# Controlador_Aforo.net
KiCad netlist of a schematic drawn in EasyEDA
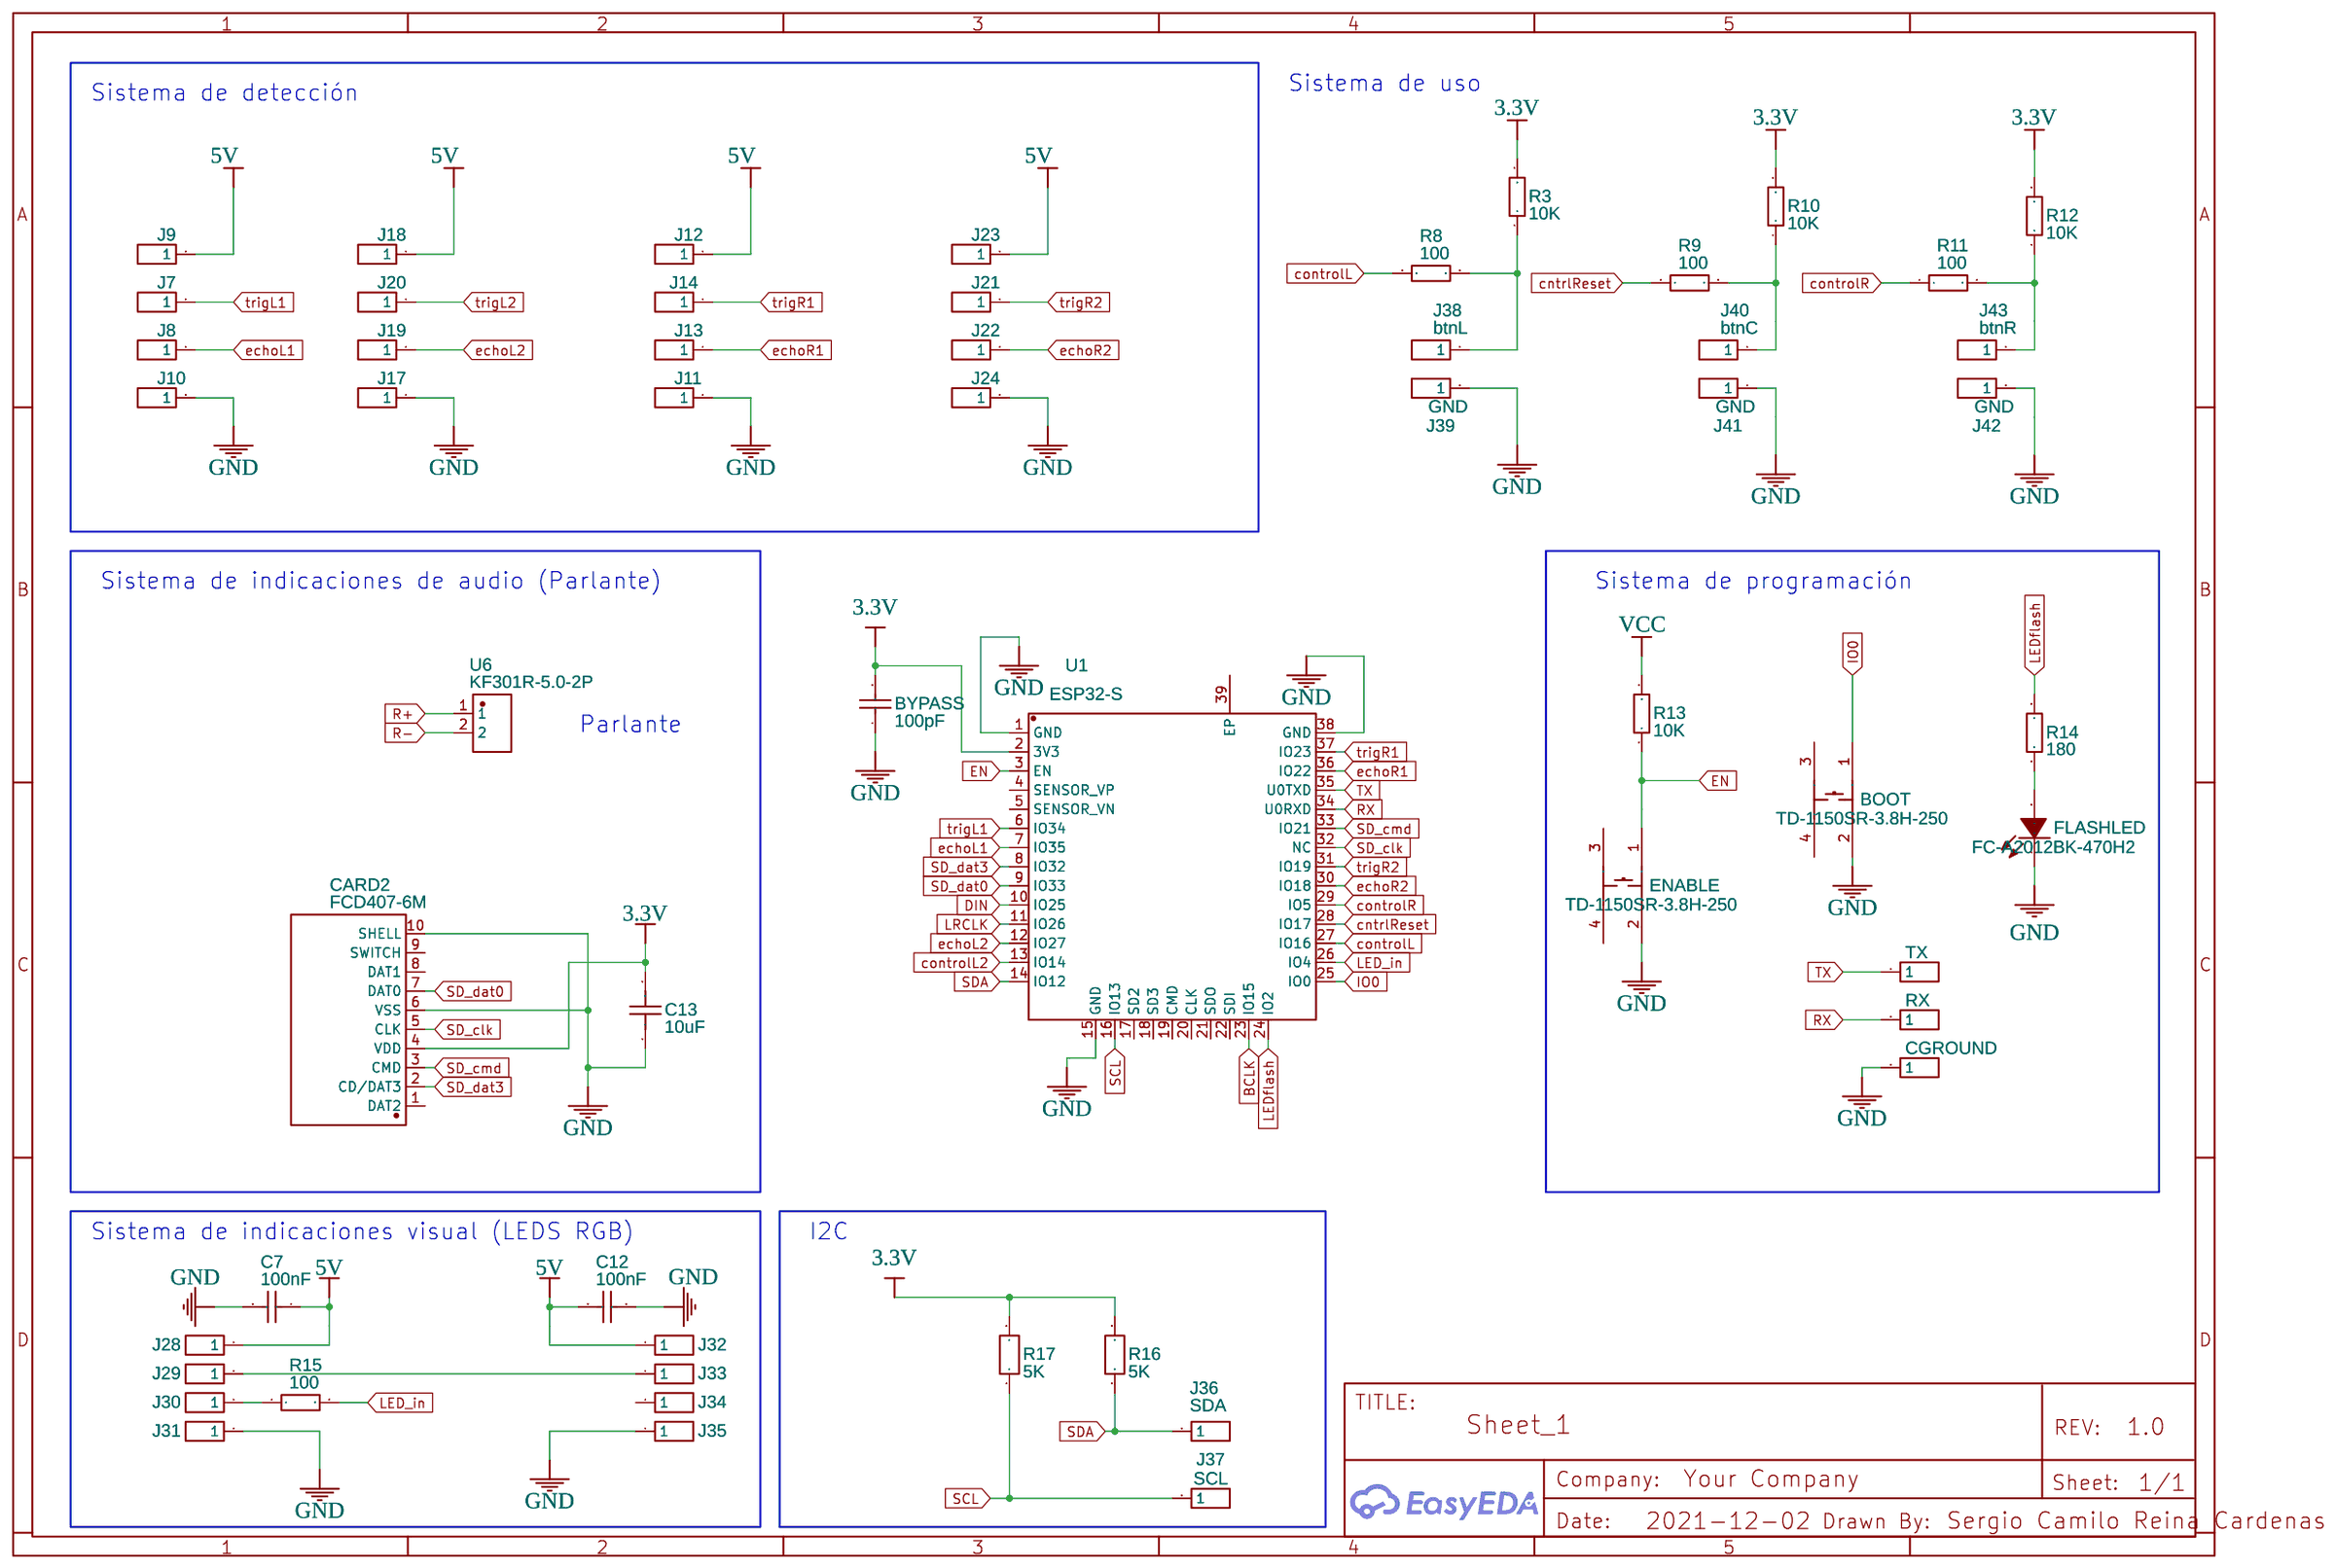
[diagram p0: Controlador_aforo]
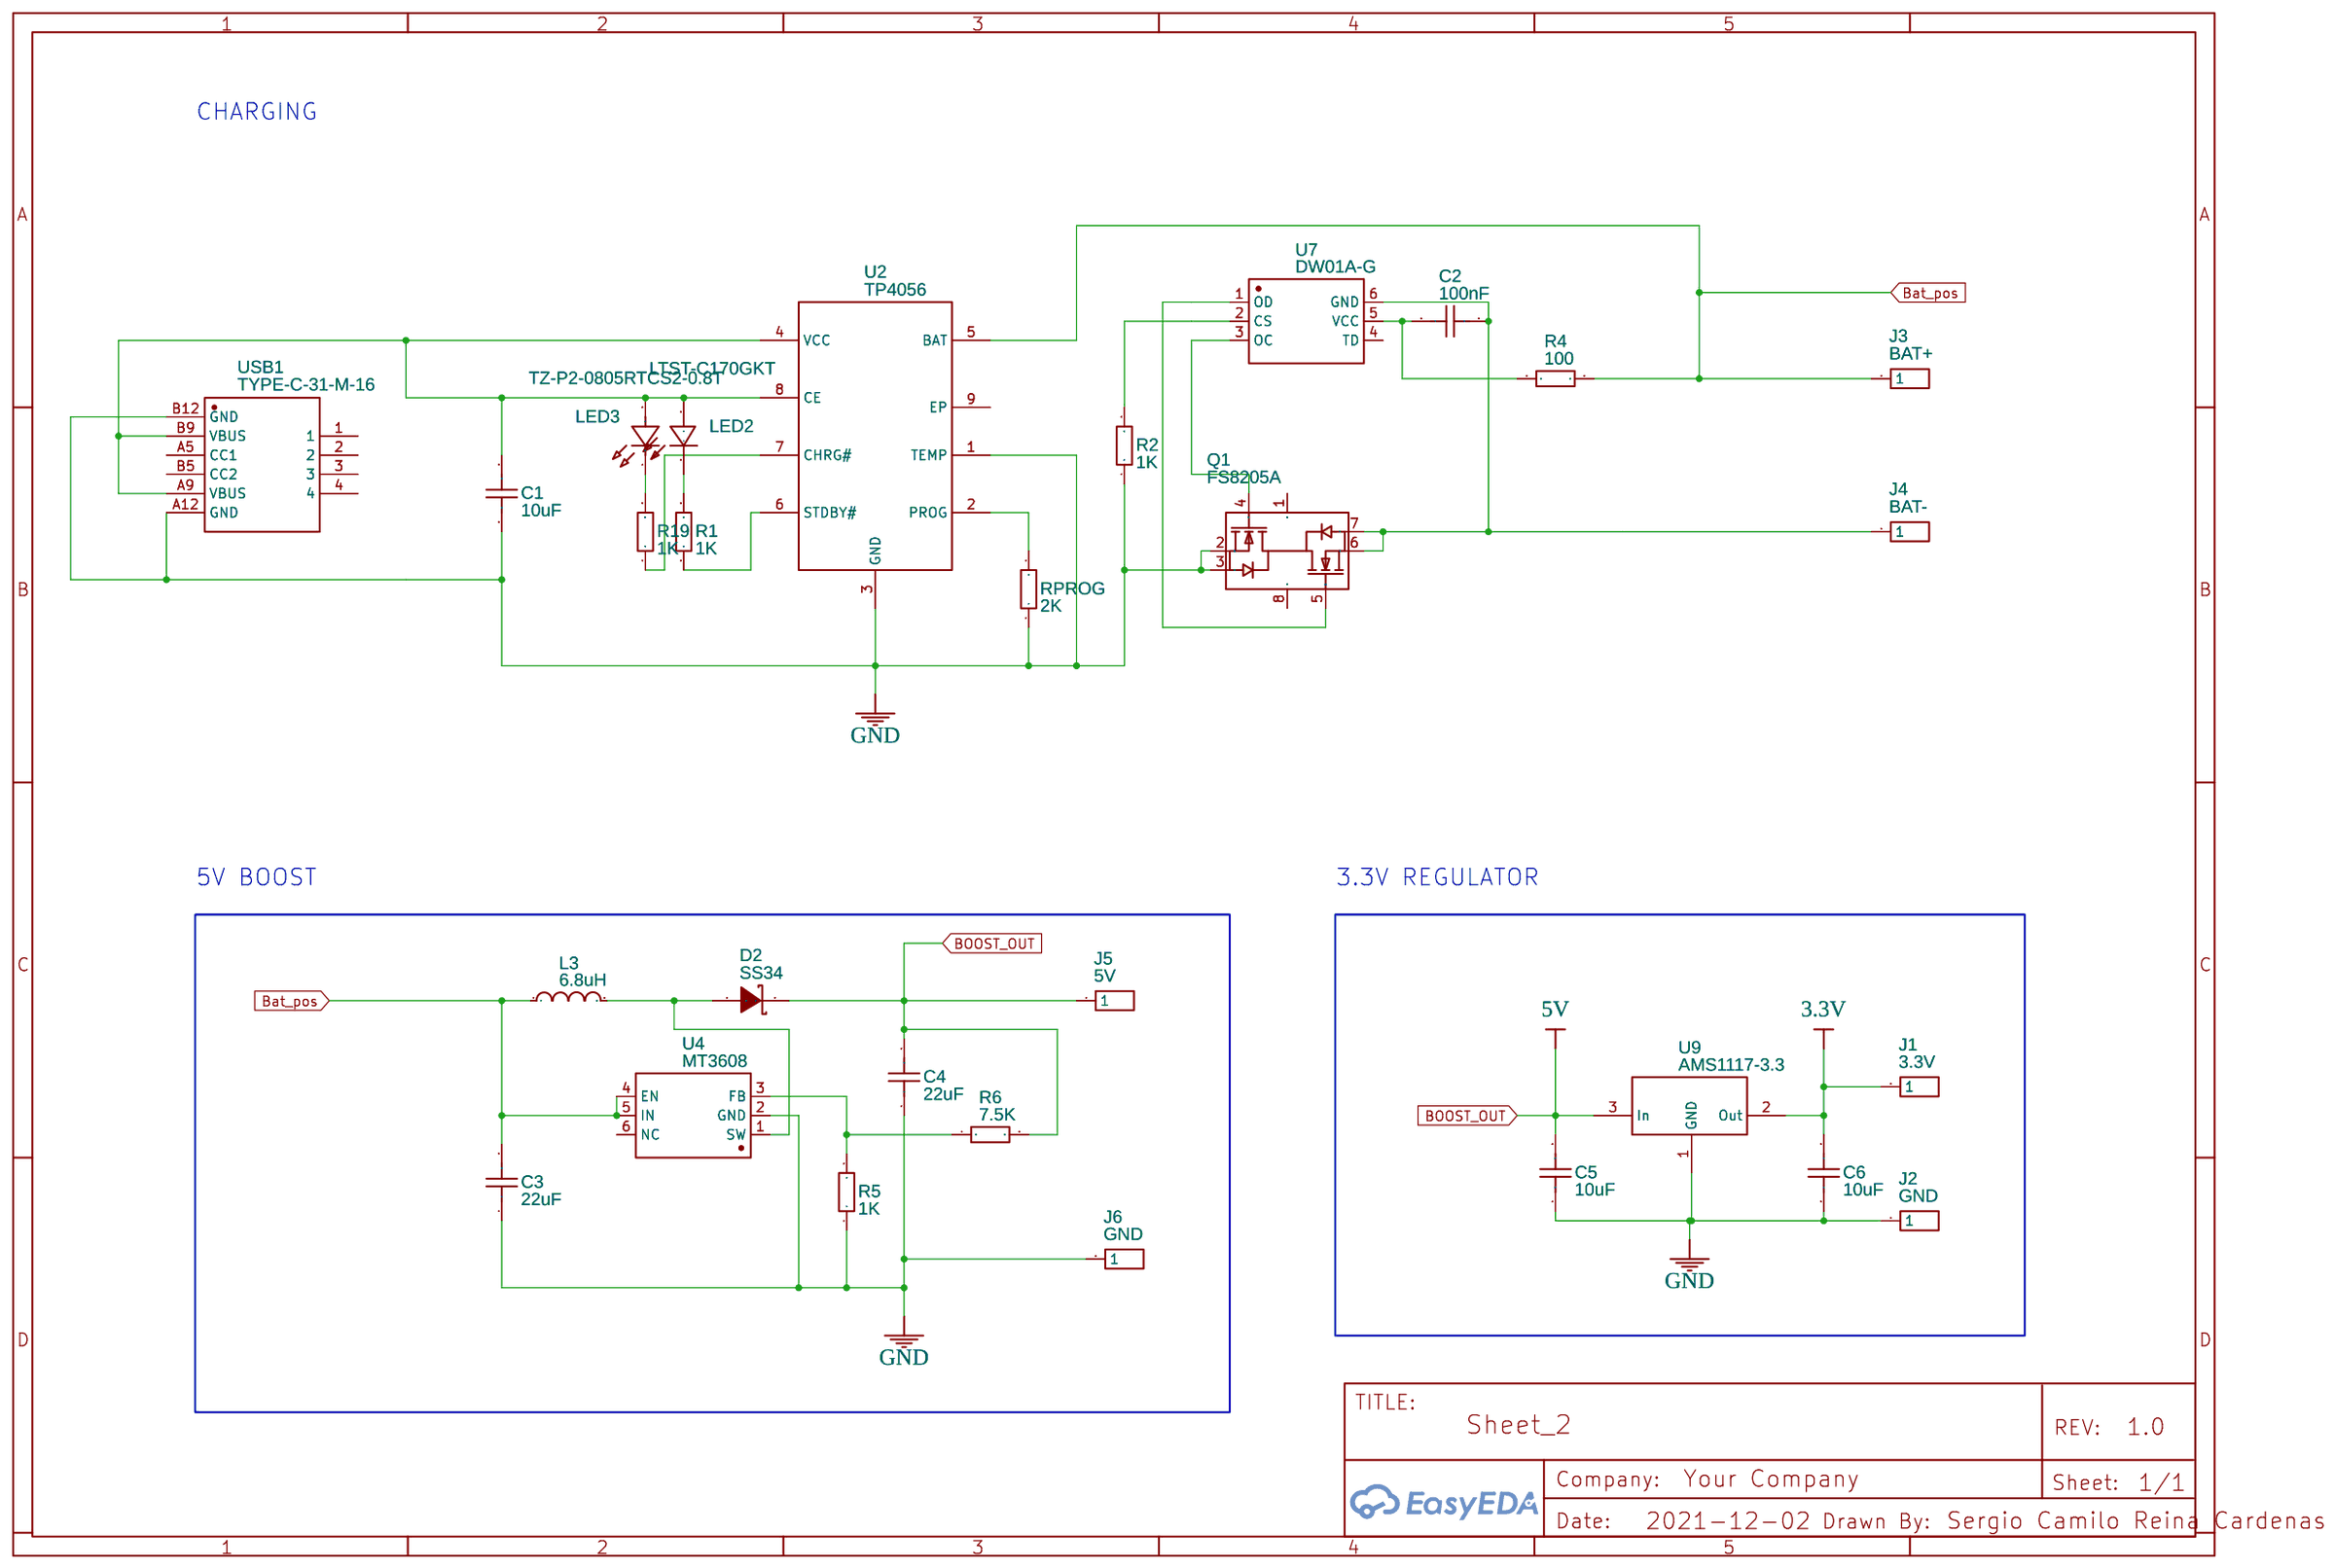
[diagram p1: Power]
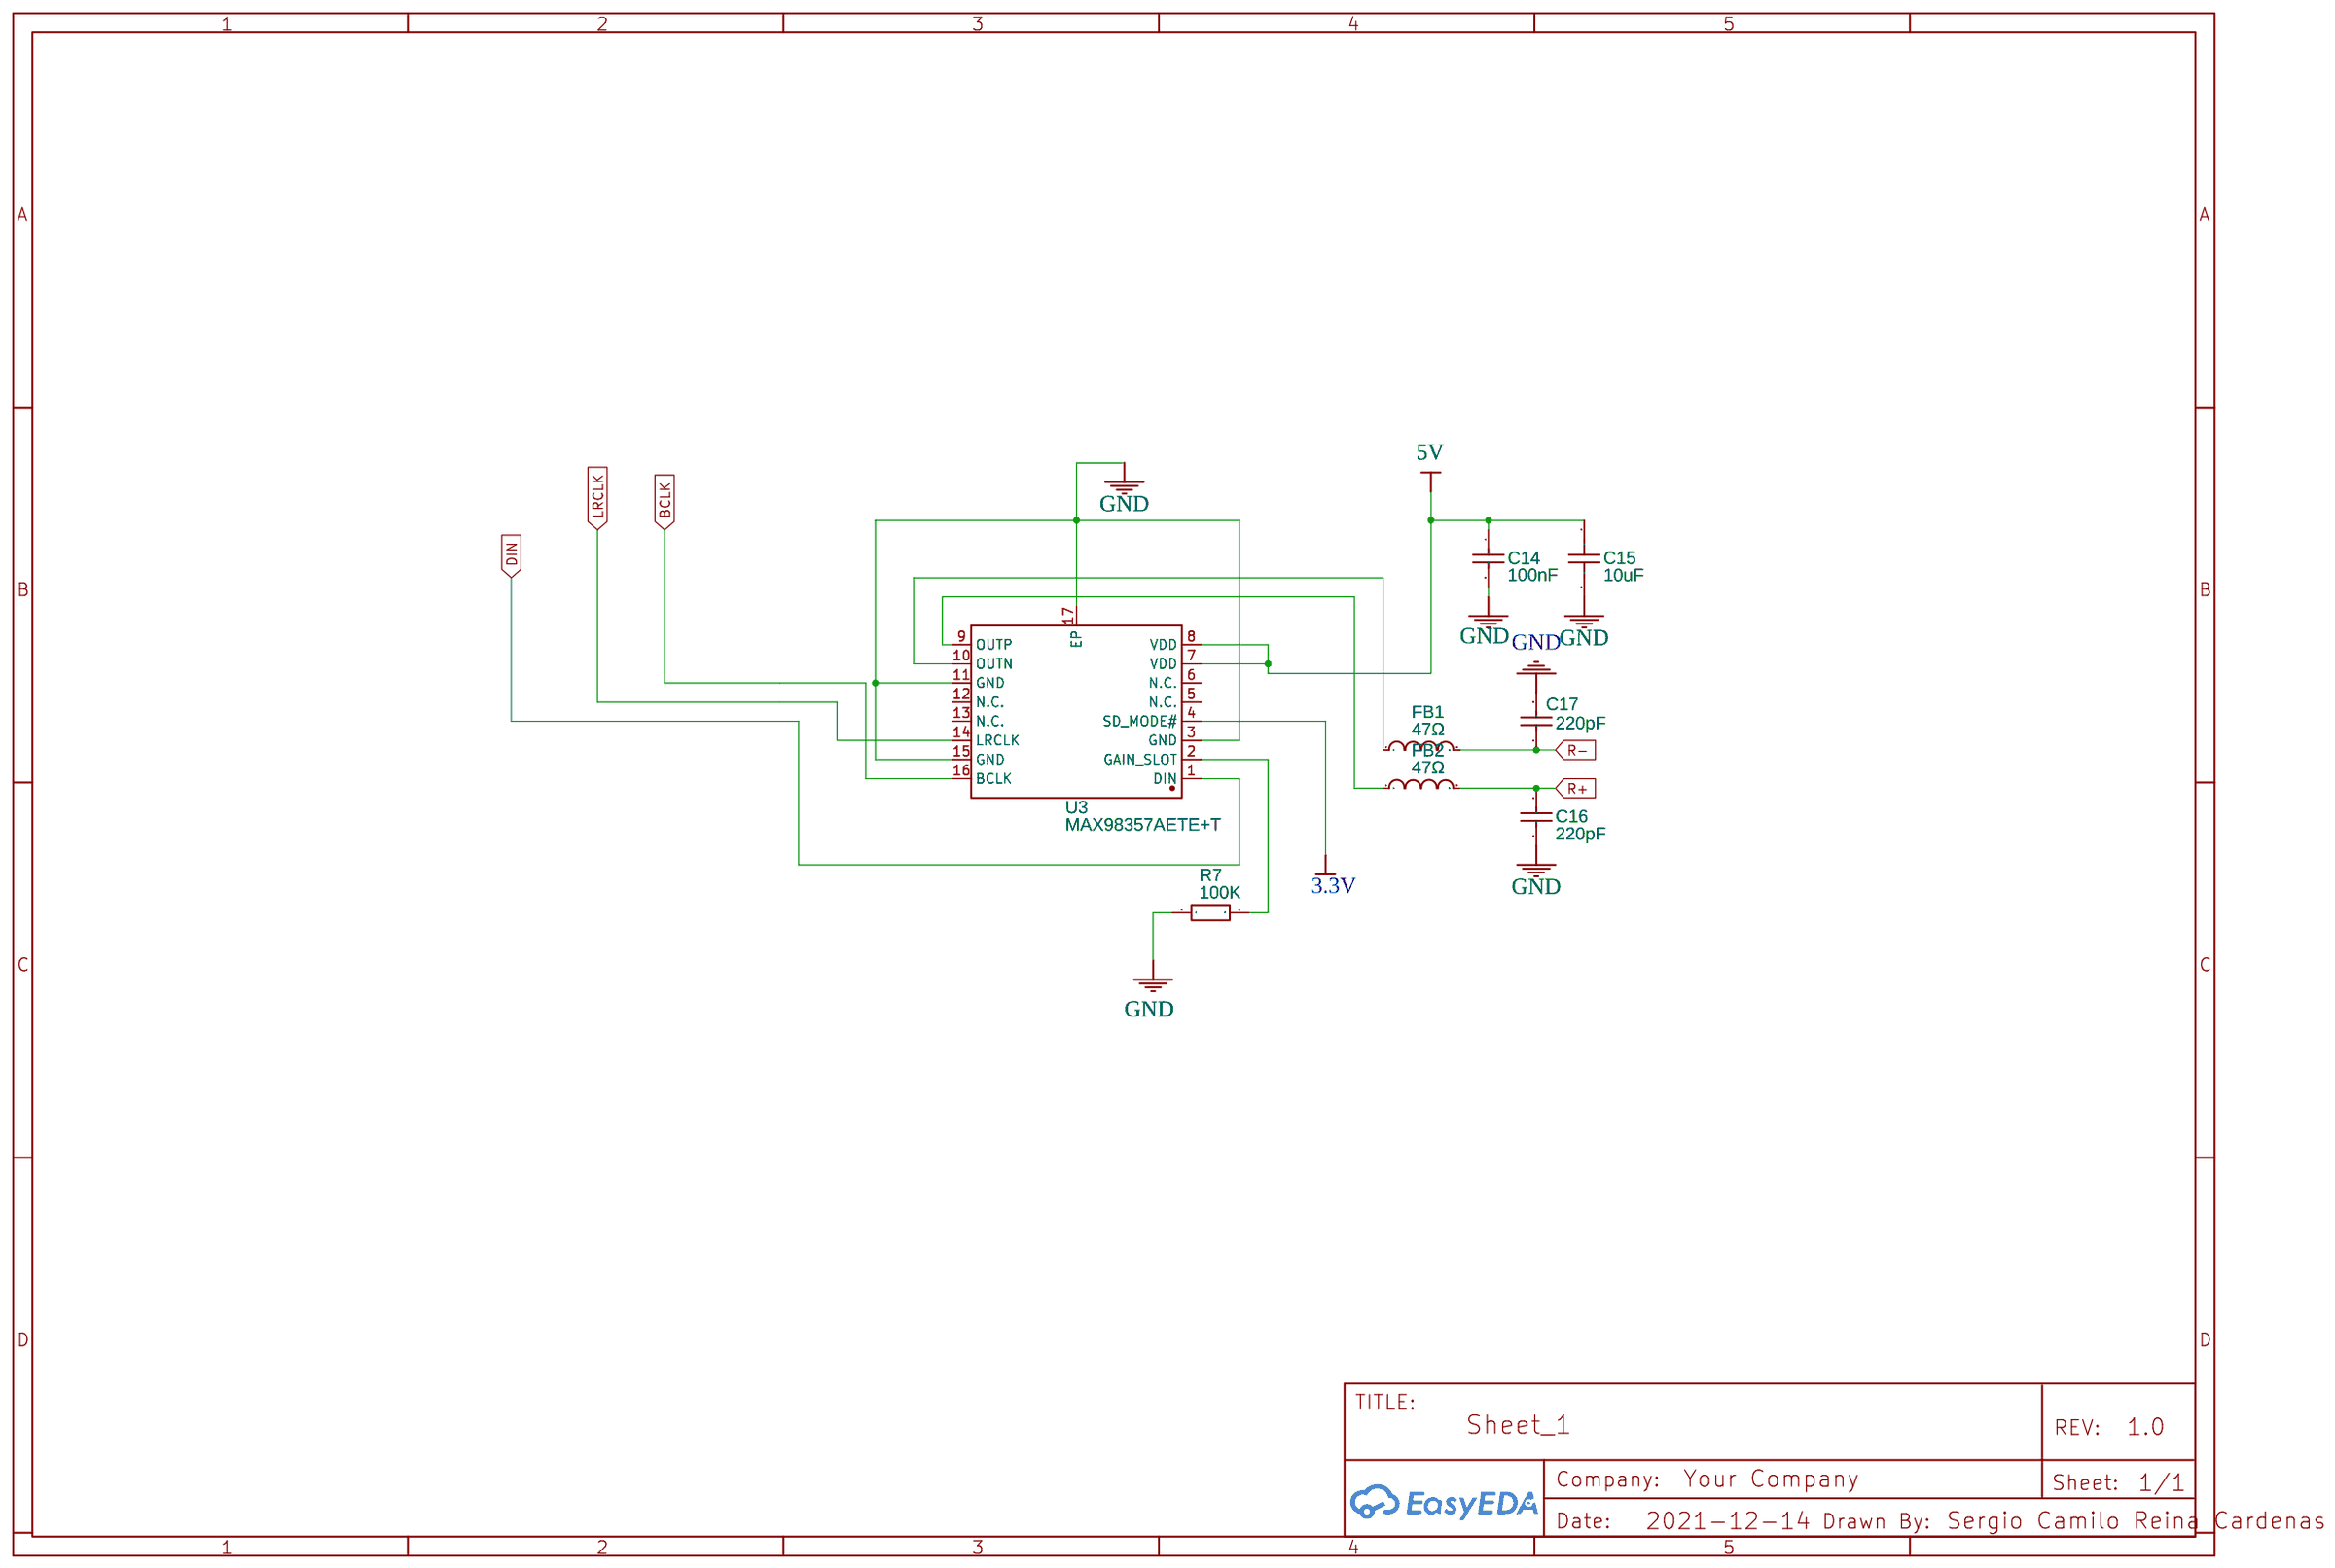
[diagram p2: Audio_amplifier]

(export (version "E")
  (design (tool "Eeschema 10.0.6"))
  (components
    (comp (ref "BOOT")
      (value "TD-1150SR-3.8H-250")
      (fields (field (name "BOM_Supplier Part") "C2905105"))
      (libsource (lib "") (part "TD-1150SR-3.8H-250_1"))
    )
    (comp (ref "BYPASS")
      (value "100pF")
      (fields
        (field (name "BOM_Manufacturer Part") "C1210N101J202T")
        (field (name "BOM_Supplier Part") "C106093")
      )
      (libsource (lib "") (part "C1210N101J202T"))
    )
    (comp (ref "C7")
      (value "100nF")
      (fields
        (field (name "BOM_Manufacturer Part") "C1210X104M501T")
        (field (name "BOM_Supplier Part") "C106106")
      )
      (libsource (lib "") (part "C1210X104M501T"))
    )
    (comp (ref "C12")
      (value "100nF")
      (fields
        (field (name "BOM_Manufacturer Part") "C1210X104M501T")
        (field (name "BOM_Supplier Part") "C106106")
      )
      (libsource (lib "") (part "C1210X104M501T"))
    )
    (comp (ref "C13")
      (value "10uF")
      (fields
        (field (name "BOM_Manufacturer Part") "0805F106M100NT")
        (field (name "BOM_Supplier Part") "C91158")
      )
      (libsource (lib "") (part "0805F106M100NT"))
    )
    (comp (ref "CARD2")
      (value "FCD407-6M")
      (fields (field (name "BOM_Supplier Part") "C456402"))
      (libsource (lib "") (part "FCD407-6M"))
    )
    (comp (ref "CGROUND")
      (value "HDR-M-2.54_1x1")
      (fields (field (name "BOM_Supplier Part") "C81276"))
      (libsource (lib "") (part "HDR-M-2.54_1x1_4"))
    )
    (comp (ref "ENABLE")
      (value "TD-1150SR-3.8H-250")
      (fields (field (name "BOM_Supplier Part") "C2905105"))
      (libsource (lib "") (part "TD-1150SR-3.8H-250"))
    )
    (comp (ref "FLASHLED")
      (value "FC-A2012BK-470H2")
      (fields (field (name "BOM_Supplier Part") "C84259"))
      (libsource (lib "") (part "FC-A2012BK-470H2"))
    )
    (comp (ref "J7")
      (value "HDR-M-2.54_1x1")
      (fields (field (name "BOM_Supplier Part") "C81276"))
      (libsource (lib "") (part "HDR-M-2.54_1x1"))
    )
    (comp (ref "J8")
      (value "HDR-M-2.54_1x1")
      (fields (field (name "BOM_Supplier Part") "C81276"))
      (libsource (lib "") (part "HDR-M-2.54_1x1"))
    )
    (comp (ref "J9")
      (value "HDR-M-2.54_1x1")
      (fields (field (name "BOM_Supplier Part") "C81276"))
      (libsource (lib "") (part "HDR-M-2.54_1x1"))
    )
    (comp (ref "J10")
      (value "HDR-M-2.54_1x1")
      (fields (field (name "BOM_Supplier Part") "C81276"))
      (libsource (lib "") (part "HDR-M-2.54_1x1"))
    )
    (comp (ref "J11")
      (value "HDR-M-2.54_1x1")
      (fields (field (name "BOM_Supplier Part") "C81276"))
      (libsource (lib "") (part "HDR-M-2.54_1x1"))
    )
    (comp (ref "J12")
      (value "HDR-M-2.54_1x1")
      (fields (field (name "BOM_Supplier Part") "C81276"))
      (libsource (lib "") (part "HDR-M-2.54_1x1"))
    )
    (comp (ref "J13")
      (value "HDR-M-2.54_1x1")
      (fields (field (name "BOM_Supplier Part") "C81276"))
      (libsource (lib "") (part "HDR-M-2.54_1x1"))
    )
    (comp (ref "J14")
      (value "HDR-M-2.54_1x1")
      (fields (field (name "BOM_Supplier Part") "C81276"))
      (libsource (lib "") (part "HDR-M-2.54_1x1"))
    )
    (comp (ref "J17")
      (value "HDR-M-2.54_1x1")
      (fields (field (name "BOM_Supplier Part") "C81276"))
      (libsource (lib "") (part "HDR-M-2.54_1x1"))
    )
    (comp (ref "J18")
      (value "HDR-M-2.54_1x1")
      (fields (field (name "BOM_Supplier Part") "C81276"))
      (libsource (lib "") (part "HDR-M-2.54_1x1"))
    )
    (comp (ref "J19")
      (value "HDR-M-2.54_1x1")
      (fields (field (name "BOM_Supplier Part") "C81276"))
      (libsource (lib "") (part "HDR-M-2.54_1x1"))
    )
    (comp (ref "J20")
      (value "HDR-M-2.54_1x1")
      (fields (field (name "BOM_Supplier Part") "C81276"))
      (libsource (lib "") (part "HDR-M-2.54_1x1"))
    )
    (comp (ref "J21")
      (value "HDR-M-2.54_1x1")
      (fields (field (name "BOM_Supplier Part") "C81276"))
      (libsource (lib "") (part "HDR-M-2.54_1x1"))
    )
    (comp (ref "J22")
      (value "HDR-M-2.54_1x1")
      (fields (field (name "BOM_Supplier Part") "C81276"))
      (libsource (lib "") (part "HDR-M-2.54_1x1"))
    )
    (comp (ref "J23")
      (value "HDR-M-2.54_1x1")
      (fields (field (name "BOM_Supplier Part") "C81276"))
      (libsource (lib "") (part "HDR-M-2.54_1x1"))
    )
    (comp (ref "J24")
      (value "HDR-M-2.54_1x1")
      (fields (field (name "BOM_Supplier Part") "C81276"))
      (libsource (lib "") (part "HDR-M-2.54_1x1"))
    )
    (comp (ref "J28")
      (value "HDR-M-2.54_1x1")
      (fields (field (name "BOM_Supplier Part") "C81276"))
      (libsource (lib "") (part "HDR-M-2.54_1x1"))
    )
    (comp (ref "J29")
      (value "HDR-M-2.54_1x1")
      (fields (field (name "BOM_Supplier Part") "C81276"))
      (libsource (lib "") (part "HDR-M-2.54_1x1"))
    )
    (comp (ref "J30")
      (value "HDR-M-2.54_1x1")
      (fields (field (name "BOM_Supplier Part") "C81276"))
      (libsource (lib "") (part "HDR-M-2.54_1x1"))
    )
    (comp (ref "J31")
      (value "HDR-M-2.54_1x1")
      (fields (field (name "BOM_Supplier Part") "C81276"))
      (libsource (lib "") (part "HDR-M-2.54_1x1"))
    )
    (comp (ref "J32")
      (value "HDR-M-2.54_1x1")
      (fields (field (name "BOM_Supplier Part") "C81276"))
      (libsource (lib "") (part "HDR-M-2.54_1x1_1"))
    )
    (comp (ref "J33")
      (value "HDR-M-2.54_1x1")
      (fields (field (name "BOM_Supplier Part") "C81276"))
      (libsource (lib "") (part "HDR-M-2.54_1x1_1"))
    )
    (comp (ref "J34")
      (value "HDR-M-2.54_1x1")
      (fields (field (name "BOM_Supplier Part") "C81276"))
      (libsource (lib "") (part "HDR-M-2.54_1x1_1"))
    )
    (comp (ref "J35")
      (value "HDR-M-2.54_1x1")
      (fields (field (name "BOM_Supplier Part") "C81276"))
      (libsource (lib "") (part "HDR-M-2.54_1x1_1"))
    )
    (comp (ref "J36")
      (value "SDA")
      (fields (field (name "BOM_Supplier Part") "C81276"))
      (libsource (lib "") (part "HDR-M-2.54_1x1_1"))
    )
    (comp (ref "J37")
      (value "SCL")
      (fields (field (name "BOM_Supplier Part") "C81276"))
      (libsource (lib "") (part "HDR-M-2.54_1x1_1"))
    )
    (comp (ref "J38")
      (value "btnL")
      (fields (field (name "BOM_Supplier Part") "C81276"))
      (libsource (lib "") (part "HDR-M-2.54_1x1"))
    )
    (comp (ref "J39")
      (value "GND")
      (fields (field (name "BOM_Supplier Part") "C81276"))
      (libsource (lib "") (part "HDR-M-2.54_1x1"))
    )
    (comp (ref "J40")
      (value "btnC")
      (fields (field (name "BOM_Supplier Part") "C81276"))
      (libsource (lib "") (part "HDR-M-2.54_1x1"))
    )
    (comp (ref "J41")
      (value "GND")
      (fields (field (name "BOM_Supplier Part") "C81276"))
      (libsource (lib "") (part "HDR-M-2.54_1x1"))
    )
    (comp (ref "J42")
      (value "GND")
      (fields (field (name "BOM_Supplier Part") "C81276"))
      (libsource (lib "") (part "HDR-M-2.54_1x1"))
    )
    (comp (ref "J43")
      (value "btnR")
      (fields (field (name "BOM_Supplier Part") "C81276"))
      (libsource (lib "") (part "HDR-M-2.54_1x1"))
    )
    (comp (ref "R3")
      (value "10K")
      (fields
        (field (name "BOM_Manufacturer Part") "RMCF0805FT10K0")
        (field (name "BOM_Supplier Part") "C237755")
      )
      (libsource (lib "") (part "RMCF0805FT10K0"))
    )
    (comp (ref "R8")
      (value "100")
      (fields
        (field (name "BOM_Manufacturer Part") "RMC08051001%N")
        (field (name "BOM_Supplier Part") "C269741")
      )
      (libsource (lib "") (part "RMC08051001%N"))
    )
    (comp (ref "R9")
      (value "100")
      (fields
        (field (name "BOM_Manufacturer Part") "RMC08051001%N")
        (field (name "BOM_Supplier Part") "C269741")
      )
      (libsource (lib "") (part "RMC08051001%N"))
    )
    (comp (ref "R10")
      (value "10K")
      (fields
        (field (name "BOM_Manufacturer Part") "RMCF0805FT10K0")
        (field (name "BOM_Supplier Part") "C237755")
      )
      (libsource (lib "") (part "RMCF0805FT10K0"))
    )
    (comp (ref "R11")
      (value "100")
      (fields
        (field (name "BOM_Manufacturer Part") "RMC08051001%N")
        (field (name "BOM_Supplier Part") "C269741")
      )
      (libsource (lib "") (part "RMC08051001%N"))
    )
    (comp (ref "R12")
      (value "10K")
      (fields
        (field (name "BOM_Manufacturer Part") "RMCF0805FT10K0")
        (field (name "BOM_Supplier Part") "C237755")
      )
      (libsource (lib "") (part "RMCF0805FT10K0"))
    )
    (comp (ref "R13")
      (value "10K")
      (fields
        (field (name "BOM_Manufacturer Part") "RMCF0805FT10K0")
        (field (name "BOM_Supplier Part") "C237755")
      )
      (libsource (lib "") (part "RMCF0805FT10K0"))
    )
    (comp (ref "R14")
      (value "180")
      (fields
        (field (name "BOM_Manufacturer Part") "HPCR0805F180RK9")
        (field (name "BOM_Supplier Part") "C365251")
      )
      (libsource (lib "") (part "HPCR0805F180RK9"))
    )
    (comp (ref "R15")
      (value "100")
      (fields
        (field (name "BOM_Manufacturer Part") "RMC08051001%N")
        (field (name "BOM_Supplier Part") "C269741")
      )
      (libsource (lib "") (part "RMC08051001%N"))
    )
    (comp (ref "R16")
      (value "5K")
      (fields
        (field (name "BOM_Manufacturer Part") "RTT055001FTP")
        (field (name "BOM_Supplier Part") "C332873")
      )
      (libsource (lib "") (part "RTT055001FTP"))
    )
    (comp (ref "R17")
      (value "5K")
      (fields
        (field (name "BOM_Manufacturer Part") "RTT055001FTP")
        (field (name "BOM_Supplier Part") "C332873")
      )
      (libsource (lib "") (part "RTT055001FTP"))
    )
    (comp (ref "RX")
      (value "HDR-M-2.54_1x1")
      (fields (field (name "BOM_Supplier Part") "C81276"))
      (libsource (lib "") (part "HDR-M-2.54_1x1_3"))
    )
    (comp (ref "TX")
      (value "HDR-M-2.54_1x1")
      (fields (field (name "BOM_Supplier Part") "C81276"))
      (libsource (lib "") (part "HDR-M-2.54_1x1_2"))
    )
    (comp (ref "U1")
      (value "ESP32-S")
      (fields (field (name "BOM_Supplier Part") "C277944"))
      (libsource (lib "") (part "ESP32-S"))
    )
    (comp (ref "U6")
      (value "KF301R-5.0-2P")
      (fields (field (name "BOM_Supplier Part") "C474883"))
      (libsource (lib "") (part "KF301R-5.0-2P"))
    )
    (comp (ref "C1")
      (value "10uF")
      (fields
        (field (name "BOM_Manufacturer Part") "CS1608X7R225K100NRB")
        (field (name "BOM_Supplier Part") "C516003")
      )
      (libsource (lib "") (part "CS1608X7R225K100NRB"))
    )
    (comp (ref "C2")
      (value "100nF")
      (fields
        (field (name "BOM_Manufacturer Part") "CS1608X7R225K100NRB")
        (field (name "BOM_Supplier Part") "C516003")
      )
      (libsource (lib "") (part "CS1608X7R225K100NRB_1"))
    )
    (comp (ref "C3")
      (value "22uF")
      (fields
        (field (name "BOM_Manufacturer Part") "CS1608X7R225K100NRB")
        (field (name "BOM_Supplier Part") "C516003")
      )
      (libsource (lib "") (part "CS1608X7R225K100NRB"))
    )
    (comp (ref "C4")
      (value "22uF")
      (fields
        (field (name "BOM_Manufacturer Part") "CS1608X7R225K100NRB")
        (field (name "BOM_Supplier Part") "C516003")
      )
      (libsource (lib "") (part "CS1608X7R225K100NRB"))
    )
    (comp (ref "C5")
      (value "10uF")
      (fields
        (field (name "BOM_Manufacturer Part") "0805F106M100NT")
        (field (name "BOM_Supplier Part") "C91158")
      )
      (libsource (lib "") (part "0805F106M100NT"))
    )
    (comp (ref "C6")
      (value "10uF")
      (fields
        (field (name "BOM_Manufacturer Part") "0805F106M100NT")
        (field (name "BOM_Supplier Part") "C91158")
      )
      (libsource (lib "") (part "0805F106M100NT"))
    )
    (comp (ref "D2")
      (value "SS34")
      (fields (field (name "BOM_Supplier Part") "C13763"))
      (libsource (lib "") (part "SS34"))
    )
    (comp (ref "J1")
      (value "3.3V")
      (fields (field (name "BOM_Supplier Part") "C81276"))
      (libsource (lib "") (part "HDR-M-2.54_1x1"))
    )
    (comp (ref "J2")
      (value "GND")
      (fields (field (name "BOM_Supplier Part") "C81276"))
      (libsource (lib "") (part "HDR-M-2.54_1x1"))
    )
    (comp (ref "J3")
      (value "BAT+")
      (fields (field (name "BOM_Supplier Part") "C81276"))
      (libsource (lib "") (part "HDR-M-2.54_1x1"))
    )
    (comp (ref "J4")
      (value "BAT-")
      (fields (field (name "BOM_Supplier Part") "C81276"))
      (libsource (lib "") (part "HDR-M-2.54_1x1"))
    )
    (comp (ref "J5")
      (value "5V")
      (fields (field (name "BOM_Supplier Part") "C81276"))
      (libsource (lib "") (part "HDR-M-2.54_1x1"))
    )
    (comp (ref "J6")
      (value "GND")
      (fields (field (name "BOM_Supplier Part") "C81276"))
      (libsource (lib "") (part "HDR-M-2.54_1x1"))
    )
    (comp (ref "L3")
      (value "6.8uH")
      (fields
        (field (name "BOM_Manufacturer Part") "SCCD32-6R8MT")
        (field (name "BOM_Supplier Part") "C532852")
      )
      (libsource (lib "") (part "SCCD32-6R8MT"))
    )
    (comp (ref "LED2")
      (value "TZ-P2-0805RTCS2-0.8T")
      (fields (field (name "BOM_Supplier Part") "C688884"))
      (libsource (lib "") (part "TZ-P2-0805RTCS2-0.8T"))
    )
    (comp (ref "LED3")
      (value "LTST-C170GKT")
      (fields (field (name "BOM_Supplier Part") "C125090"))
      (libsource (lib "") (part "LTST-C170GKT"))
    )
    (comp (ref "Q1")
      (value "FS8205A")
      (fields (field (name "BOM_Supplier Part") "C16052"))
      (libsource (lib "") (part "FS8205A"))
    )
    (comp (ref "R1")
      (value "1K")
      (fields
        (field (name "BOM_Manufacturer Part") "CR0805J80102G")
        (field (name "BOM_Supplier Part") "C101925")
      )
      (libsource (lib "") (part "CR0805J80102G"))
    )
    (comp (ref "R2")
      (value "1K")
      (fields
        (field (name "BOM_Manufacturer Part") "CR0805J80102G")
        (field (name "BOM_Supplier Part") "C101925")
      )
      (libsource (lib "") (part "CR0805J80102G"))
    )
    (comp (ref "R4")
      (value "100")
      (fields
        (field (name "BOM_Manufacturer Part") "RMC08051001%N")
        (field (name "BOM_Supplier Part") "C269741")
      )
      (libsource (lib "") (part "RMC08051001%N"))
    )
    (comp (ref "R5")
      (value "1K")
      (fields
        (field (name "BOM_Manufacturer Part") "CR0805J80102G")
        (field (name "BOM_Supplier Part") "C101925")
      )
      (libsource (lib "") (part "CR0805J80102G"))
    )
    (comp (ref "R6")
      (value "7.5K")
      (fields
        (field (name "BOM_Manufacturer Part") "RMCF0805JT7K50")
        (field (name "BOM_Supplier Part") "C237142")
      )
      (libsource (lib "") (part "RMCF0805JT7K50"))
    )
    (comp (ref "R19")
      (value "1K")
      (fields
        (field (name "BOM_Manufacturer Part") "CR0805J80102G")
        (field (name "BOM_Supplier Part") "C101925")
      )
      (libsource (lib "") (part "CR0805J80102G"))
    )
    (comp (ref "RPROG")
      (value "2K")
      (fields
        (field (name "BOM_Manufacturer Part") "CR0805J80202G")
        (field (name "BOM_Supplier Part") "C101963")
      )
      (libsource (lib "") (part "CR0805J80202G"))
    )
    (comp (ref "U2")
      (value "TP4056")
      (fields (field (name "BOM_Supplier Part") "C16581"))
      (libsource (lib "") (part "TP4056"))
    )
    (comp (ref "U4")
      (value "MT3608")
      (fields (field (name "BOM_Supplier Part") "C84817"))
      (libsource (lib "") (part "MT3608"))
    )
    (comp (ref "U7")
      (value "DW01A-G")
      (fields (field (name "BOM_Supplier Part") "C61503"))
      (libsource (lib "") (part "DW01A-G"))
    )
    (comp (ref "U9")
      (value "AMS1117-3.3")
      (fields (field (name "BOM_Supplier Part") "C6186"))
      (libsource (lib "") (part "Unknown_875_-230"))
    )
    (comp (ref "USB1")
      (value "TYPE-C-31-M-16")
      (fields (field (name "BOM_Supplier Part") "C283541"))
      (libsource (lib "") (part "TYPE-C-31-M-16"))
    )
    (comp (ref "C14")
      (value "100nF")
      (fields
        (field (name "BOM_Manufacturer Part") "C1210X104M501T")
        (field (name "BOM_Supplier Part") "C106106")
      )
      (libsource (lib "") (part "C1210X104M501T"))
    )
    (comp (ref "C15")
      (value "10uF")
      (fields
        (field (name "BOM_Manufacturer Part") "0805F106M100NT")
        (field (name "BOM_Supplier Part") "C91158")
      )
      (libsource (lib "") (part "0805F106M100NT"))
    )
    (comp (ref "C16")
      (value "220pF")
      (fields
        (field (name "BOM_Manufacturer Part") "CL21B221KBANNNC")
        (field (name "BOM_Supplier Part") "C53172")
      )
      (libsource (lib "") (part "CL21B221KBANNNC"))
    )
    (comp (ref "C17")
      (value "220pF")
      (fields
        (field (name "BOM_Manufacturer Part") "CL21B221KBANNNC")
        (field (name "BOM_Supplier Part") "C53172")
      )
      (libsource (lib "") (part "CL21B221KBANNNC"))
    )
    (comp (ref "FB1")
      (value "47Ω")
      (fields
        (field (name "BOM_Manufacturer Part") "BK2125HS470-T")
        (field (name "BOM_Supplier Part") "C92871")
      )
      (libsource (lib "") (part "BK2125HS470-T"))
    )
    (comp (ref "FB2")
      (value "47Ω")
      (fields
        (field (name "BOM_Manufacturer Part") "BK2125HS470-T")
        (field (name "BOM_Supplier Part") "C92871")
      )
      (libsource (lib "") (part "BK2125HS470-T"))
    )
    (comp (ref "R7")
      (value "100K")
      (fields
        (field (name "BOM_Manufacturer Part") "AR05BTDW1003")
        (field (name "BOM_Supplier Part") "C319972")
      )
      (libsource (lib "") (part "AR05BTDW1003"))
    )
    (comp (ref "U3")
      (value "MAX98357AETE+T")
      (fields (field (name "BOM_Supplier Part") "C910544"))
      (libsource (lib "") (part "MAX98357AETE+T"))
    )
  )
  (nets
    (net (code "1") (name "3.3V") (class "Default")
      (node (ref "BYPASS") (pin "2") (pinfunction "2_2") (pintype "input"))
      (node (ref "C13") (pin "2") (pinfunction "2_2") (pintype "unspecified"))
      (node (ref "C6") (pin "2") (pinfunction "2_2") (pintype "unspecified"))
      (node (ref "CARD2") (pin "4") (pinfunction "VDD_4") (pintype "unspecified"))
      (node (ref "J1") (pin "1") (pinfunction "1_1") (pintype "input"))
      (node (ref "R10") (pin "2") (pinfunction "2_2") (pintype "unspecified"))
      (node (ref "R12") (pin "2") (pinfunction "2_2") (pintype "unspecified"))
      (node (ref "R16") (pin "2") (pinfunction "2_2") (pintype "unspecified"))
      (node (ref "R17") (pin "2") (pinfunction "2_2") (pintype "unspecified"))
      (node (ref "R3") (pin "2") (pinfunction "2_2") (pintype "unspecified"))
      (node (ref "U1") (pin "2") (pinfunction "3V3_2") (pintype "unspecified"))
      (node (ref "U3") (pin "4") (pinfunction "SD_MODE#_4") (pintype "unspecified"))
      (node (ref "U9") (pin "2") (pinfunction "Out_2") (pintype "unspecified"))
    )
    (net (code "2") (name "BCLK") (class "Default")
      (node (ref "U1") (pin "23") (pinfunction "IO15_23") (pintype "unspecified"))
      (node (ref "U3") (pin "16") (pinfunction "BCLK_16") (pintype "unspecified"))
    )
    (net (code "3") (name "BOOST_OUT") (class "Default")
      (node (ref "C12") (pin "2") (pinfunction "2_2") (pintype "input"))
      (node (ref "C14") (pin "1") (pinfunction "1_1") (pintype "input"))
      (node (ref "C15") (pin "2") (pinfunction "2_2") (pintype "unspecified"))
      (node (ref "C4") (pin "2") (pinfunction "2_2") (pintype "unspecified"))
      (node (ref "C5") (pin "2") (pinfunction "2_2") (pintype "unspecified"))
      (node (ref "C7") (pin "1") (pinfunction "1_1") (pintype "input"))
      (node (ref "D2") (pin "2") (pinfunction "K_2") (pintype "unspecified"))
      (node (ref "J12") (pin "1") (pinfunction "1_1") (pintype "input"))
      (node (ref "J18") (pin "1") (pinfunction "1_1") (pintype "input"))
      (node (ref "J23") (pin "1") (pinfunction "1_1") (pintype "input"))
      (node (ref "J28") (pin "1") (pinfunction "1_1") (pintype "input"))
      (node (ref "J32") (pin "1") (pinfunction "1_1") (pintype "input"))
      (node (ref "J5") (pin "1") (pinfunction "1_1") (pintype "input"))
      (node (ref "J9") (pin "1") (pinfunction "1_1") (pintype "input"))
      (node (ref "R6") (pin "2") (pinfunction "2_2") (pintype "unspecified"))
      (node (ref "U3") (pin "7") (pinfunction "VDD_7") (pintype "unspecified"))
      (node (ref "U3") (pin "8") (pinfunction "VDD_8") (pintype "unspecified"))
      (node (ref "U9") (pin "3") (pinfunction "In_3") (pintype "unspecified"))
    )
    (net (code "4") (name "Bat_pos") (class "Default")
      (node (ref "C3") (pin "2") (pinfunction "2_2") (pintype "unspecified"))
      (node (ref "J3") (pin "1") (pinfunction "1_1") (pintype "input"))
      (node (ref "L3") (pin "1") (pinfunction "1_1") (pintype "unspecified"))
      (node (ref "R4") (pin "2") (pinfunction "2_2") (pintype "unspecified"))
      (node (ref "U2") (pin "5") (pinfunction "BAT_5") (pintype "unspecified"))
      (node (ref "U4") (pin "4") (pinfunction "EN_4") (pintype "unspecified"))
      (node (ref "U4") (pin "5") (pinfunction "IN_5") (pintype "unspecified"))
    )
    (net (code "5") (name "DIN") (class "Default")
      (node (ref "U1") (pin "10") (pinfunction "IO25_10") (pintype "unspecified"))
      (node (ref "U3") (pin "1") (pinfunction "DIN_1") (pintype "unspecified"))
    )
    (net (code "6") (name "EN") (class "Default")
      (node (ref "ENABLE") (pin "1") (pinfunction "1_1") (pintype "unspecified"))
      (node (ref "R13") (pin "1") (pinfunction "1_1") (pintype "unspecified"))
      (node (ref "U1") (pin "3") (pinfunction "EN_3") (pintype "unspecified"))
    )
    (net (code "7") (name "GND") (class "Default")
      (node (ref "BOOT") (pin "2") (pinfunction "2_2") (pintype "unspecified"))
      (node (ref "BYPASS") (pin "1") (pinfunction "1_1") (pintype "input"))
      (node (ref "C1") (pin "1") (pinfunction "1_1") (pintype "unspecified"))
      (node (ref "C12") (pin "1") (pinfunction "1_1") (pintype "input"))
      (node (ref "C13") (pin "1") (pinfunction "1_1") (pintype "unspecified"))
      (node (ref "C14") (pin "2") (pinfunction "2_2") (pintype "input"))
      (node (ref "C15") (pin "1") (pinfunction "1_1") (pintype "unspecified"))
      (node (ref "C16") (pin "1") (pinfunction "1_1") (pintype "input"))
      (node (ref "C17") (pin "2") (pinfunction "2_2") (pintype "input"))
      (node (ref "C3") (pin "1") (pinfunction "1_1") (pintype "unspecified"))
      (node (ref "C4") (pin "1") (pinfunction "1_1") (pintype "unspecified"))
      (node (ref "C5") (pin "1") (pinfunction "1_1") (pintype "unspecified"))
      (node (ref "C6") (pin "1") (pinfunction "1_1") (pintype "unspecified"))
      (node (ref "C7") (pin "2") (pinfunction "2_2") (pintype "input"))
      (node (ref "CARD2") (pin "10") (pinfunction "SHELL_10") (pintype "unspecified"))
      (node (ref "CARD2") (pin "6") (pinfunction "VSS_6") (pintype "unspecified"))
      (node (ref "CGROUND") (pin "1") (pinfunction "1_1") (pintype "input"))
      (node (ref "ENABLE") (pin "2") (pinfunction "2_2") (pintype "unspecified"))
      (node (ref "FLASHLED") (pin "1") (pinfunction "-_1") (pintype "unspecified"))
      (node (ref "J10") (pin "1") (pinfunction "1_1") (pintype "input"))
      (node (ref "J11") (pin "1") (pinfunction "1_1") (pintype "input"))
      (node (ref "J17") (pin "1") (pinfunction "1_1") (pintype "input"))
      (node (ref "J2") (pin "1") (pinfunction "1_1") (pintype "input"))
      (node (ref "J24") (pin "1") (pinfunction "1_1") (pintype "input"))
      (node (ref "J31") (pin "1") (pinfunction "1_1") (pintype "input"))
      (node (ref "J35") (pin "1") (pinfunction "1_1") (pintype "input"))
      (node (ref "J39") (pin "1") (pinfunction "1_1") (pintype "input"))
      (node (ref "J41") (pin "1") (pinfunction "1_1") (pintype "input"))
      (node (ref "J42") (pin "1") (pinfunction "1_1") (pintype "input"))
      (node (ref "J6") (pin "1") (pinfunction "1_1") (pintype "input"))
      (node (ref "Q1") (pin "2") (pinfunction "S1_2") (pintype "unspecified"))
      (node (ref "Q1") (pin "3") (pinfunction "S1_3") (pintype "unspecified"))
      (node (ref "R2") (pin "1") (pinfunction "1_1") (pintype "unspecified"))
      (node (ref "R5") (pin "1") (pinfunction "1_1") (pintype "unspecified"))
      (node (ref "R7") (pin "1") (pinfunction "1_1") (pintype "unspecified"))
      (node (ref "RPROG") (pin "1") (pinfunction "1_1") (pintype "input"))
      (node (ref "U1") (pin "1") (pinfunction "GND_1") (pintype "unspecified"))
      (node (ref "U1") (pin "15") (pinfunction "GND_15") (pintype "unspecified"))
      (node (ref "U1") (pin "38") (pinfunction "GND_38") (pintype "unspecified"))
      (node (ref "U2") (pin "1") (pinfunction "TEMP_1") (pintype "unspecified"))
      (node (ref "U2") (pin "3") (pinfunction "GND_3") (pintype "unspecified"))
      (node (ref "U3") (pin "11") (pinfunction "GND_11") (pintype "unspecified"))
      (node (ref "U3") (pin "15") (pinfunction "GND_15") (pintype "unspecified"))
      (node (ref "U3") (pin "17") (pinfunction "EP_17") (pintype "unspecified"))
      (node (ref "U3") (pin "3") (pinfunction "GND_3") (pintype "unspecified"))
      (node (ref "U4") (pin "2") (pinfunction "GND_2") (pintype "unspecified"))
      (node (ref "U9") (pin "1") (pinfunction "GND_1") (pintype "unspecified"))
      (node (ref "USB1") (pin "A12") (pinfunction "GND_A12") (pintype "unspecified"))
      (node (ref "USB1") (pin "B12") (pinfunction "GND_B12") (pintype "unspecified"))
    )
    (net (code "8") (name "IO0") (class "Default")
      (node (ref "BOOT") (pin "1") (pinfunction "1_1") (pintype "unspecified"))
      (node (ref "U1") (pin "25") (pinfunction "IO0_25") (pintype "unspecified"))
    )
    (net (code "9") (name "LED_in") (class "Default")
      (node (ref "R15") (pin "2") (pinfunction "2_2") (pintype "unspecified"))
      (node (ref "U1") (pin "26") (pinfunction "IO4_26") (pintype "unspecified"))
    )
    (net (code "10") (name "LEDflash") (class "Default")
      (node (ref "R14") (pin "2") (pinfunction "2_2") (pintype "unspecified"))
      (node (ref "U1") (pin "24") (pinfunction "IO2_24") (pintype "unspecified"))
    )
    (net (code "11") (name "LRCLK") (class "Default")
      (node (ref "U1") (pin "11") (pinfunction "IO26_11") (pintype "unspecified"))
      (node (ref "U3") (pin "14") (pinfunction "LRCLK_14") (pintype "unspecified"))
    )
    (net (code "12") (name "Net-(D2-A)") (class "Default")
      (node (ref "D2") (pin "1") (pinfunction "A_1") (pintype "unspecified"))
      (node (ref "L3") (pin "2") (pinfunction "2_2") (pintype "unspecified"))
      (node (ref "U4") (pin "1") (pinfunction "SW_1") (pintype "unspecified"))
    )
    (net (code "13") (name "Net-(FLASHLED-+)") (class "Default")
      (node (ref "FLASHLED") (pin "2") (pinfunction "+_2") (pintype "unspecified"))
      (node (ref "R14") (pin "1") (pinfunction "1_1") (pintype "unspecified"))
    )
    (net (code "14") (name "Net-(J29-Pad1)") (class "Default")
      (node (ref "J29") (pin "1") (pinfunction "1_1") (pintype "input"))
      (node (ref "J33") (pin "1") (pinfunction "1_1") (pintype "input"))
    )
    (net (code "15") (name "Net-(J30-Pad1)") (class "Default")
      (node (ref "J30") (pin "1") (pinfunction "1_1") (pintype "input"))
      (node (ref "R15") (pin "1") (pinfunction "1_1") (pintype "unspecified"))
    )
    (net (code "16") (name "Net-(J38-Pad1)") (class "Default")
      (node (ref "J38") (pin "1") (pinfunction "1_1") (pintype "input"))
      (node (ref "R3") (pin "1") (pinfunction "1_1") (pintype "unspecified"))
      (node (ref "R8") (pin "2") (pinfunction "2_2") (pintype "unspecified"))
    )
    (net (code "17") (name "Net-(J40-Pad1)") (class "Default")
      (node (ref "J40") (pin "1") (pinfunction "1_1") (pintype "input"))
      (node (ref "R10") (pin "1") (pinfunction "1_1") (pintype "unspecified"))
      (node (ref "R9") (pin "2") (pinfunction "2_2") (pintype "unspecified"))
    )
    (net (code "18") (name "Net-(J43-Pad1)") (class "Default")
      (node (ref "J43") (pin "1") (pinfunction "1_1") (pintype "input"))
      (node (ref "R11") (pin "2") (pinfunction "2_2") (pintype "unspecified"))
      (node (ref "R12") (pin "1") (pinfunction "1_1") (pintype "unspecified"))
    )
    (net (code "19") (name "Net-(LED2-A)") (class "Default")
      (node (ref "C1") (pin "2") (pinfunction "2_2") (pintype "unspecified"))
      (node (ref "LED2") (pin "2") (pinfunction "A_2") (pintype "unspecified"))
      (node (ref "LED3") (pin "2") (pinfunction "+_2") (pintype "unspecified"))
      (node (ref "U2") (pin "4") (pinfunction "VCC_4") (pintype "unspecified"))
      (node (ref "U2") (pin "8") (pinfunction "CE_8") (pintype "unspecified"))
      (node (ref "USB1") (pin "A9") (pinfunction "VBUS_A9") (pintype "unspecified"))
      (node (ref "USB1") (pin "B9") (pinfunction "VBUS_B9") (pintype "unspecified"))
    )
    (net (code "20") (name "Net-(LED2-K)") (class "Default")
      (node (ref "LED2") (pin "1") (pinfunction "K_1") (pintype "unspecified"))
      (node (ref "R19") (pin "2") (pinfunction "2_2") (pintype "unspecified"))
    )
    (net (code "21") (name "Net-(LED3--)") (class "Default")
      (node (ref "LED3") (pin "1") (pinfunction "-_1") (pintype "unspecified"))
      (node (ref "R1") (pin "2") (pinfunction "2_2") (pintype "unspecified"))
    )
    (net (code "22") (name "Net-(Q1-G1)") (class "Default")
      (node (ref "Q1") (pin "4") (pinfunction "G1_4") (pintype "unspecified"))
      (node (ref "U7") (pin "3") (pinfunction "OC_3") (pintype "unspecified"))
    )
    (net (code "23") (name "Net-(Q1-G2)") (class "Default")
      (node (ref "Q1") (pin "5") (pinfunction "G2_5") (pintype "unspecified"))
      (node (ref "U7") (pin "1") (pinfunction "OD_1") (pintype "unspecified"))
    )
    (net (code "24") (name "Net-(U2-CHRG#)") (class "Default")
      (node (ref "R19") (pin "1") (pinfunction "1_1") (pintype "unspecified"))
      (node (ref "U2") (pin "7") (pinfunction "CHRG#_7") (pintype "unspecified"))
    )
    (net (code "25") (name "Net-(U2-PROG)") (class "Default")
      (node (ref "RPROG") (pin "2") (pinfunction "2_2") (pintype "input"))
      (node (ref "U2") (pin "2") (pinfunction "PROG_2") (pintype "unspecified"))
    )
    (net (code "26") (name "Net-(U2-STDBY#)") (class "Default")
      (node (ref "R1") (pin "1") (pinfunction "1_1") (pintype "unspecified"))
      (node (ref "U2") (pin "6") (pinfunction "STDBY#_6") (pintype "unspecified"))
    )
    (net (code "27") (name "Net-(U3-GAIN_SLOT)") (class "Default")
      (node (ref "R7") (pin "2") (pinfunction "2_2") (pintype "unspecified"))
      (node (ref "U3") (pin "2") (pinfunction "GAIN_SLOT_2") (pintype "unspecified"))
    )
    (net (code "28") (name "Net-(U3-OUTN)") (class "Default")
      (node (ref "FB1") (pin "1") (pinfunction "1_1") (pintype "unspecified"))
      (node (ref "U3") (pin "10") (pinfunction "OUTN_10") (pintype "unspecified"))
    )
    (net (code "29") (name "Net-(U3-OUTP)") (class "Default")
      (node (ref "FB2") (pin "1") (pinfunction "1_1") (pintype "unspecified"))
      (node (ref "U3") (pin "9") (pinfunction "OUTP_9") (pintype "unspecified"))
    )
    (net (code "30") (name "Net-(U4-FB)") (class "Default")
      (node (ref "R5") (pin "2") (pinfunction "2_2") (pintype "unspecified"))
      (node (ref "R6") (pin "1") (pinfunction "1_1") (pintype "unspecified"))
      (node (ref "U4") (pin "3") (pinfunction "FB_3") (pintype "unspecified"))
    )
    (net (code "31") (name "Net-(U7-CS)") (class "Default")
      (node (ref "R2") (pin "2") (pinfunction "2_2") (pintype "unspecified"))
      (node (ref "U7") (pin "2") (pinfunction "CS_2") (pintype "unspecified"))
    )
    (net (code "32") (name "Net-(U7-GND)") (class "Default")
      (node (ref "C2") (pin "1") (pinfunction "1_1") (pintype "unspecified"))
      (node (ref "J4") (pin "1") (pinfunction "1_1") (pintype "input"))
      (node (ref "Q1") (pin "6") (pinfunction "S2_6") (pintype "unspecified"))
      (node (ref "Q1") (pin "7") (pinfunction "S2_7") (pintype "unspecified"))
      (node (ref "U7") (pin "6") (pinfunction "GND_6") (pintype "unspecified"))
    )
    (net (code "33") (name "Net-(U7-VCC)") (class "Default")
      (node (ref "C2") (pin "2") (pinfunction "2_2") (pintype "unspecified"))
      (node (ref "R4") (pin "1") (pinfunction "1_1") (pintype "unspecified"))
      (node (ref "U7") (pin "5") (pinfunction "VCC_5") (pintype "unspecified"))
    )
    (net (code "34") (name "R+") (class "Default")
      (node (ref "C16") (pin "2") (pinfunction "2_2") (pintype "input"))
      (node (ref "FB2") (pin "2") (pinfunction "2_2") (pintype "unspecified"))
      (node (ref "U6") (pin "1") (pinfunction "1_1") (pintype "unspecified"))
    )
    (net (code "35") (name "R-") (class "Default")
      (node (ref "C17") (pin "1") (pinfunction "1_1") (pintype "input"))
      (node (ref "FB1") (pin "2") (pinfunction "2_2") (pintype "unspecified"))
      (node (ref "U6") (pin "2") (pinfunction "2_2") (pintype "unspecified"))
    )
    (net (code "36") (name "RX") (class "Default")
      (node (ref "RX") (pin "1") (pinfunction "1_1") (pintype "input"))
      (node (ref "U1") (pin "34") (pinfunction "U0RXD_34") (pintype "unspecified"))
    )
    (net (code "37") (name "SCL") (class "Default")
      (node (ref "J37") (pin "1") (pinfunction "1_1") (pintype "input"))
      (node (ref "R17") (pin "1") (pinfunction "1_1") (pintype "unspecified"))
      (node (ref "U1") (pin "16") (pinfunction "IO13_16") (pintype "unspecified"))
    )
    (net (code "38") (name "SDA") (class "Default")
      (node (ref "J36") (pin "1") (pinfunction "1_1") (pintype "input"))
      (node (ref "R16") (pin "1") (pinfunction "1_1") (pintype "unspecified"))
      (node (ref "U1") (pin "14") (pinfunction "IO12_14") (pintype "unspecified"))
    )
    (net (code "39") (name "SD_clk") (class "Default")
      (node (ref "CARD2") (pin "5") (pinfunction "CLK_5") (pintype "unspecified"))
      (node (ref "U1") (pin "32") (pinfunction "NC_32") (pintype "unspecified"))
    )
    (net (code "40") (name "SD_cmd") (class "Default")
      (node (ref "CARD2") (pin "3") (pinfunction "CMD_3") (pintype "unspecified"))
      (node (ref "U1") (pin "33") (pinfunction "IO21_33") (pintype "unspecified"))
    )
    (net (code "41") (name "SD_dat0") (class "Default")
      (node (ref "CARD2") (pin "7") (pinfunction "DAT0_7") (pintype "unspecified"))
      (node (ref "U1") (pin "9") (pinfunction "IO33_9") (pintype "unspecified"))
    )
    (net (code "42") (name "SD_dat3") (class "Default")
      (node (ref "CARD2") (pin "2") (pinfunction "CD/DAT3_2") (pintype "unspecified"))
      (node (ref "U1") (pin "8") (pinfunction "IO32_8") (pintype "unspecified"))
    )
    (net (code "43") (name "TX") (class "Default")
      (node (ref "TX") (pin "1") (pinfunction "1_1") (pintype "input"))
      (node (ref "U1") (pin "35") (pinfunction "U0TXD_35") (pintype "unspecified"))
    )
    (net (code "44") (name "VCC") (class "Default")
      (node (ref "R13") (pin "2") (pinfunction "2_2") (pintype "unspecified"))
    )
    (net (code "45") (name "cntrlReset") (class "Default")
      (node (ref "R9") (pin "1") (pinfunction "1_1") (pintype "unspecified"))
      (node (ref "U1") (pin "28") (pinfunction "IO17_28") (pintype "unspecified"))
    )
    (net (code "46") (name "controlL") (class "Default")
      (node (ref "R8") (pin "1") (pinfunction "1_1") (pintype "unspecified"))
      (node (ref "U1") (pin "27") (pinfunction "IO16_27") (pintype "unspecified"))
    )
    (net (code "47") (name "controlL2") (class "Default")
      (node (ref "U1") (pin "13") (pinfunction "IO14_13") (pintype "unspecified"))
    )
    (net (code "48") (name "controlR") (class "Default")
      (node (ref "R11") (pin "1") (pinfunction "1_1") (pintype "unspecified"))
      (node (ref "U1") (pin "29") (pinfunction "IO5_29") (pintype "unspecified"))
    )
    (net (code "49") (name "echoL1") (class "Default")
      (node (ref "J8") (pin "1") (pinfunction "1_1") (pintype "input"))
      (node (ref "U1") (pin "7") (pinfunction "IO35_7") (pintype "unspecified"))
    )
    (net (code "50") (name "echoL2") (class "Default")
      (node (ref "J19") (pin "1") (pinfunction "1_1") (pintype "input"))
      (node (ref "U1") (pin "12") (pinfunction "IO27_12") (pintype "unspecified"))
    )
    (net (code "51") (name "echoR1") (class "Default")
      (node (ref "J13") (pin "1") (pinfunction "1_1") (pintype "input"))
      (node (ref "U1") (pin "36") (pinfunction "IO22_36") (pintype "unspecified"))
    )
    (net (code "52") (name "echoR2") (class "Default")
      (node (ref "J22") (pin "1") (pinfunction "1_1") (pintype "input"))
      (node (ref "U1") (pin "30") (pinfunction "IO18_30") (pintype "unspecified"))
    )
    (net (code "53") (name "trigL1") (class "Default")
      (node (ref "J7") (pin "1") (pinfunction "1_1") (pintype "input"))
      (node (ref "U1") (pin "6") (pinfunction "IO34_6") (pintype "unspecified"))
    )
    (net (code "54") (name "trigL2") (class "Default")
      (node (ref "J20") (pin "1") (pinfunction "1_1") (pintype "input"))
    )
    (net (code "55") (name "trigR1") (class "Default")
      (node (ref "J14") (pin "1") (pinfunction "1_1") (pintype "input"))
      (node (ref "U1") (pin "37") (pinfunction "IO23_37") (pintype "unspecified"))
    )
    (net (code "56") (name "trigR2") (class "Default")
      (node (ref "J21") (pin "1") (pinfunction "1_1") (pintype "input"))
      (node (ref "U1") (pin "31") (pinfunction "IO19_31") (pintype "unspecified"))
    )
    (net (code "57") (name "unconnected-(BOOT-Pad3)") (class "Default")
      (node (ref "BOOT") (pin "3") (pinfunction "3_3") (pintype "unspecified"))
    )
    (net (code "58") (name "unconnected-(BOOT-Pad4)") (class "Default")
      (node (ref "BOOT") (pin "4") (pinfunction "4_4") (pintype "unspecified"))
    )
    (net (code "59") (name "unconnected-(CARD2-DAT1-Pad8)") (class "Default")
      (node (ref "CARD2") (pin "8") (pinfunction "DAT1_8") (pintype "unspecified"))
    )
    (net (code "60") (name "unconnected-(CARD2-DAT2-Pad1)") (class "Default")
      (node (ref "CARD2") (pin "1") (pinfunction "DAT2_1") (pintype "unspecified"))
    )
    (net (code "61") (name "unconnected-(CARD2-SWITCH-Pad9)") (class "Default")
      (node (ref "CARD2") (pin "9") (pinfunction "SWITCH_9") (pintype "unspecified"))
    )
    (net (code "62") (name "unconnected-(ENABLE-Pad3)") (class "Default")
      (node (ref "ENABLE") (pin "3") (pinfunction "3_3") (pintype "unspecified"))
    )
    (net (code "63") (name "unconnected-(ENABLE-Pad4)") (class "Default")
      (node (ref "ENABLE") (pin "4") (pinfunction "4_4") (pintype "unspecified"))
    )
    (net (code "64") (name "unconnected-(J34-Pad1)") (class "Default")
      (node (ref "J34") (pin "1") (pinfunction "1_1") (pintype "input"))
    )
    (net (code "65") (name "unconnected-(Q1-D12-Pad1)") (class "Default")
      (node (ref "Q1") (pin "1") (pinfunction "D12_1") (pintype "unspecified"))
    )
    (net (code "66") (name "unconnected-(Q1-D12-Pad8)") (class "Default")
      (node (ref "Q1") (pin "8") (pinfunction "D12_8") (pintype "unspecified"))
    )
    (net (code "67") (name "unconnected-(U1-CLK-Pad20)") (class "Default")
      (node (ref "U1") (pin "20") (pinfunction "CLK_20") (pintype "unspecified"))
    )
    (net (code "68") (name "unconnected-(U1-CMD-Pad19)") (class "Default")
      (node (ref "U1") (pin "19") (pinfunction "CMD_19") (pintype "unspecified"))
    )
    (net (code "69") (name "unconnected-(U1-EP-Pad39)") (class "Default")
      (node (ref "U1") (pin "39") (pinfunction "EP_39") (pintype "unspecified"))
    )
    (net (code "70") (name "unconnected-(U1-SD2-Pad17)") (class "Default")
      (node (ref "U1") (pin "17") (pinfunction "SD2_17") (pintype "unspecified"))
    )
    (net (code "71") (name "unconnected-(U1-SD3-Pad18)") (class "Default")
      (node (ref "U1") (pin "18") (pinfunction "SD3_18") (pintype "unspecified"))
    )
    (net (code "72") (name "unconnected-(U1-SDI-Pad22)") (class "Default")
      (node (ref "U1") (pin "22") (pinfunction "SDI_22") (pintype "unspecified"))
    )
    (net (code "73") (name "unconnected-(U1-SDO-Pad21)") (class "Default")
      (node (ref "U1") (pin "21") (pinfunction "SDO_21") (pintype "unspecified"))
    )
    (net (code "74") (name "unconnected-(U1-SENSOR_VN-Pad5)") (class "Default")
      (node (ref "U1") (pin "5") (pinfunction "SENSOR_VN_5") (pintype "unspecified"))
    )
    (net (code "75") (name "unconnected-(U1-SENSOR_VP-Pad4)") (class "Default")
      (node (ref "U1") (pin "4") (pinfunction "SENSOR_VP_4") (pintype "unspecified"))
    )
    (net (code "76") (name "unconnected-(U2-EP-Pad9)") (class "Default")
      (node (ref "U2") (pin "9") (pinfunction "EP_9") (pintype "unspecified"))
    )
    (net (code "77") (name "unconnected-(U3-N.C.-Pad5)") (class "Default")
      (node (ref "U3") (pin "5") (pinfunction "N.C._5") (pintype "unspecified"))
    )
    (net (code "78") (name "unconnected-(U3-N.C.-Pad6)") (class "Default")
      (node (ref "U3") (pin "6") (pinfunction "N.C._6") (pintype "unspecified"))
    )
    (net (code "79") (name "unconnected-(U3-N.C.-Pad12)") (class "Default")
      (node (ref "U3") (pin "12") (pinfunction "N.C._12") (pintype "unspecified"))
    )
    (net (code "80") (name "unconnected-(U3-N.C.-Pad13)") (class "Default")
      (node (ref "U3") (pin "13") (pinfunction "N.C._13") (pintype "unspecified"))
    )
    (net (code "81") (name "unconnected-(U4-NC-Pad6)") (class "Default")
      (node (ref "U4") (pin "6") (pinfunction "NC_6") (pintype "unspecified"))
    )
    (net (code "82") (name "unconnected-(U7-TD-Pad4)") (class "Default")
      (node (ref "U7") (pin "4") (pinfunction "TD_4") (pintype "unspecified"))
    )
    (net (code "83") (name "unconnected-(USB1-CC1-PadA5)") (class "Default")
      (node (ref "USB1") (pin "A5") (pinfunction "CC1_A5") (pintype "unspecified"))
    )
    (net (code "84") (name "unconnected-(USB1-CC2-PadB5)") (class "Default")
      (node (ref "USB1") (pin "B5") (pinfunction "CC2_B5") (pintype "unspecified"))
    )
    (net (code "85") (name "unconnected-(USB1-Pad1)") (class "Default")
      (node (ref "USB1") (pin "1") (pinfunction "1_1") (pintype "unspecified"))
    )
    (net (code "86") (name "unconnected-(USB1-Pad2)") (class "Default")
      (node (ref "USB1") (pin "2") (pinfunction "2_2") (pintype "unspecified"))
    )
    (net (code "87") (name "unconnected-(USB1-Pad3)") (class "Default")
      (node (ref "USB1") (pin "3") (pinfunction "3_3") (pintype "unspecified"))
    )
    (net (code "88") (name "unconnected-(USB1-Pad4)") (class "Default")
      (node (ref "USB1") (pin "4") (pinfunction "4_4") (pintype "unspecified"))
    )
  )
)
